# Motor.net
KiCad netlist of a schematic drawn in Altium Designer
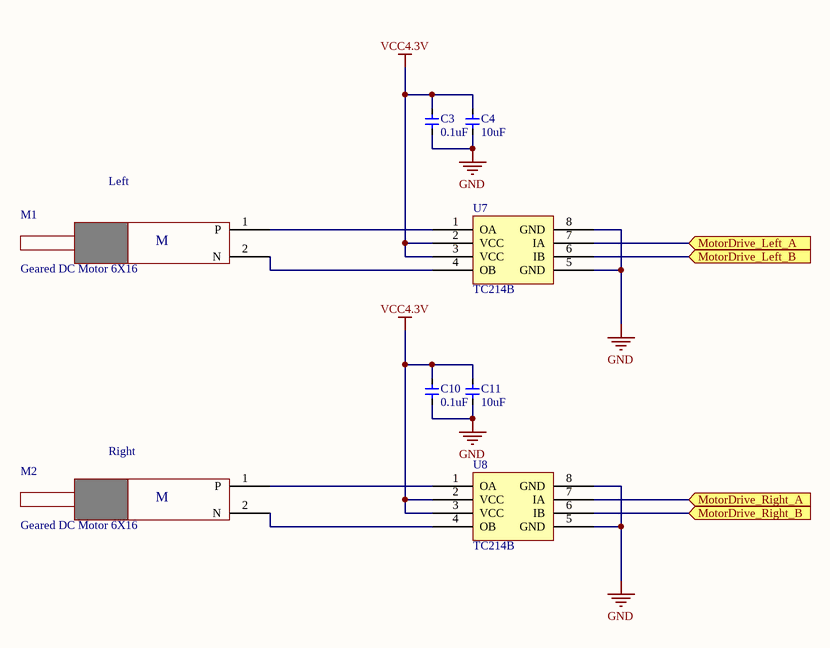
[diagram p0: Motor.SchDoc]

(export (version "E")
  (design (tool "Eeschema 10.0.6"))
  (components
    (comp (ref "C3")
      (value "0.1uF")
      (footprint "PCB_PassiveCap:CAP_0603")
      (description "Capacitor")
      (fields (field (name "Comment") "Cap_0603"))
      (libsource (lib "SCH_Passive") (part "Cap_0603"))
    )
    (comp (ref "C4")
      (value "10uF")
      (footprint "PCB_PassiveCap:CAP_0603")
      (description "Capacitor")
      (fields (field (name "Comment") "Cap_0603"))
      (libsource (lib "SCH_Passive") (part "Cap_0603"))
    )
    (comp (ref "C10")
      (value "0.1uF")
      (footprint "PCB_PassiveCap:CAP_0603")
      (description "Capacitor")
      (fields (field (name "Comment") "Cap_0603"))
      (libsource (lib "SCH_Passive") (part "Cap_0603"))
    )
    (comp (ref "C11")
      (value "10uF")
      (footprint "PCB_PassiveCap:CAP_0603")
      (description "Capacitor")
      (fields (field (name "Comment") "Cap_0603"))
      (libsource (lib "SCH_Passive") (part "Cap_0603"))
    )
    (comp (ref "M1")
      (value "Geared DC Motor 6X16")
      (footprint "Geared_DC_Motor_6X16")
      (description "Geared DC Motor, 6mm D, L=16mm")
      (libsource (lib "SCH_Mechanical") (part "GearMotor_DC_6X16"))
    )
    (comp (ref "M2")
      (value "Geared DC Motor 6X16")
      (footprint "Geared_DC_Motor_6X16")
      (description "Geared DC Motor, 6mm D, L=16mm")
      (libsource (lib "SCH_Mechanical") (part "GearMotor_DC_6X16"))
    )
    (comp (ref "U7")
      (value "TC214B")
      (footprint "PCB_IntegratedCircuit:SOP_E150_8")
      (description "DC Motor Driver 1 Channel  (Cheap Replacement of L9110)")
      (libsource (lib "SCH_IntegratedCircuit") (part "TC214B"))
    )
    (comp (ref "U8")
      (value "TC214B")
      (footprint "PCB_IntegratedCircuit:SOP_E150_8")
      (description "DC Motor Driver 1 Channel  (Cheap Replacement of L9110)")
      (libsource (lib "SCH_IntegratedCircuit") (part "TC214B"))
    )
  )
  (nets
    (net (code "1") (name "/MotorDrive_Left_A") (class "Default")
      (node (ref "U7") (pin "7") (pinfunction "IA_7") (pintype "passive"))
    )
    (net (code "2") (name "/MotorDrive_Left_B") (class "Default")
      (node (ref "U7") (pin "6") (pinfunction "IB_6") (pintype "passive"))
    )
    (net (code "3") (name "/MotorDrive_Right_A") (class "Default")
      (node (ref "U8") (pin "7") (pinfunction "IA_7") (pintype "passive"))
    )
    (net (code "4") (name "/MotorDrive_Right_B") (class "Default")
      (node (ref "U8") (pin "6") (pinfunction "IB_6") (pintype "passive"))
    )
    (net (code "5") (name "GND") (class "Default")
      (node (ref "C10") (pin "1") (pinfunction "1_1") (pintype "passive"))
      (node (ref "C11") (pin "1") (pinfunction "1_1") (pintype "passive"))
      (node (ref "C3") (pin "1") (pinfunction "1_1") (pintype "passive"))
      (node (ref "C4") (pin "1") (pinfunction "1_1") (pintype "passive"))
      (node (ref "U7") (pin "5") (pinfunction "GND_5") (pintype "passive"))
      (node (ref "U7") (pin "8") (pinfunction "GND_8") (pintype "passive"))
      (node (ref "U8") (pin "5") (pinfunction "GND_5") (pintype "passive"))
      (node (ref "U8") (pin "8") (pinfunction "GND_8") (pintype "passive"))
    )
    (net (code "6") (name "Net-(M1-N)") (class "Default")
      (node (ref "M1") (pin "2") (pinfunction "N_2") (pintype "passive"))
      (node (ref "U7") (pin "4") (pinfunction "OB_4") (pintype "passive"))
    )
    (net (code "7") (name "Net-(M1-P)") (class "Default")
      (node (ref "M1") (pin "1") (pinfunction "P_1") (pintype "passive"))
      (node (ref "U7") (pin "1") (pinfunction "OA_1") (pintype "passive"))
    )
    (net (code "8") (name "Net-(M2-N)") (class "Default")
      (node (ref "M2") (pin "2") (pinfunction "N_2") (pintype "passive"))
      (node (ref "U8") (pin "4") (pinfunction "OB_4") (pintype "passive"))
    )
    (net (code "9") (name "Net-(M2-P)") (class "Default")
      (node (ref "M2") (pin "1") (pinfunction "P_1") (pintype "passive"))
      (node (ref "U8") (pin "1") (pinfunction "OA_1") (pintype "passive"))
    )
    (net (code "10") (name "VCC4.3V") (class "Default")
      (node (ref "C10") (pin "2") (pinfunction "2_2") (pintype "passive"))
      (node (ref "C11") (pin "2") (pinfunction "2_2") (pintype "passive"))
      (node (ref "C3") (pin "2") (pinfunction "2_2") (pintype "passive"))
      (node (ref "C4") (pin "2") (pinfunction "2_2") (pintype "passive"))
      (node (ref "U7") (pin "2") (pinfunction "VCC_2") (pintype "passive"))
      (node (ref "U7") (pin "3") (pinfunction "VCC_3") (pintype "passive"))
      (node (ref "U8") (pin "2") (pinfunction "VCC_2") (pintype "passive"))
      (node (ref "U8") (pin "3") (pinfunction "VCC_3") (pintype "passive"))
    )
  )
)
